# USB.net
KiCad netlist of a schematic drawn in Altium Designer
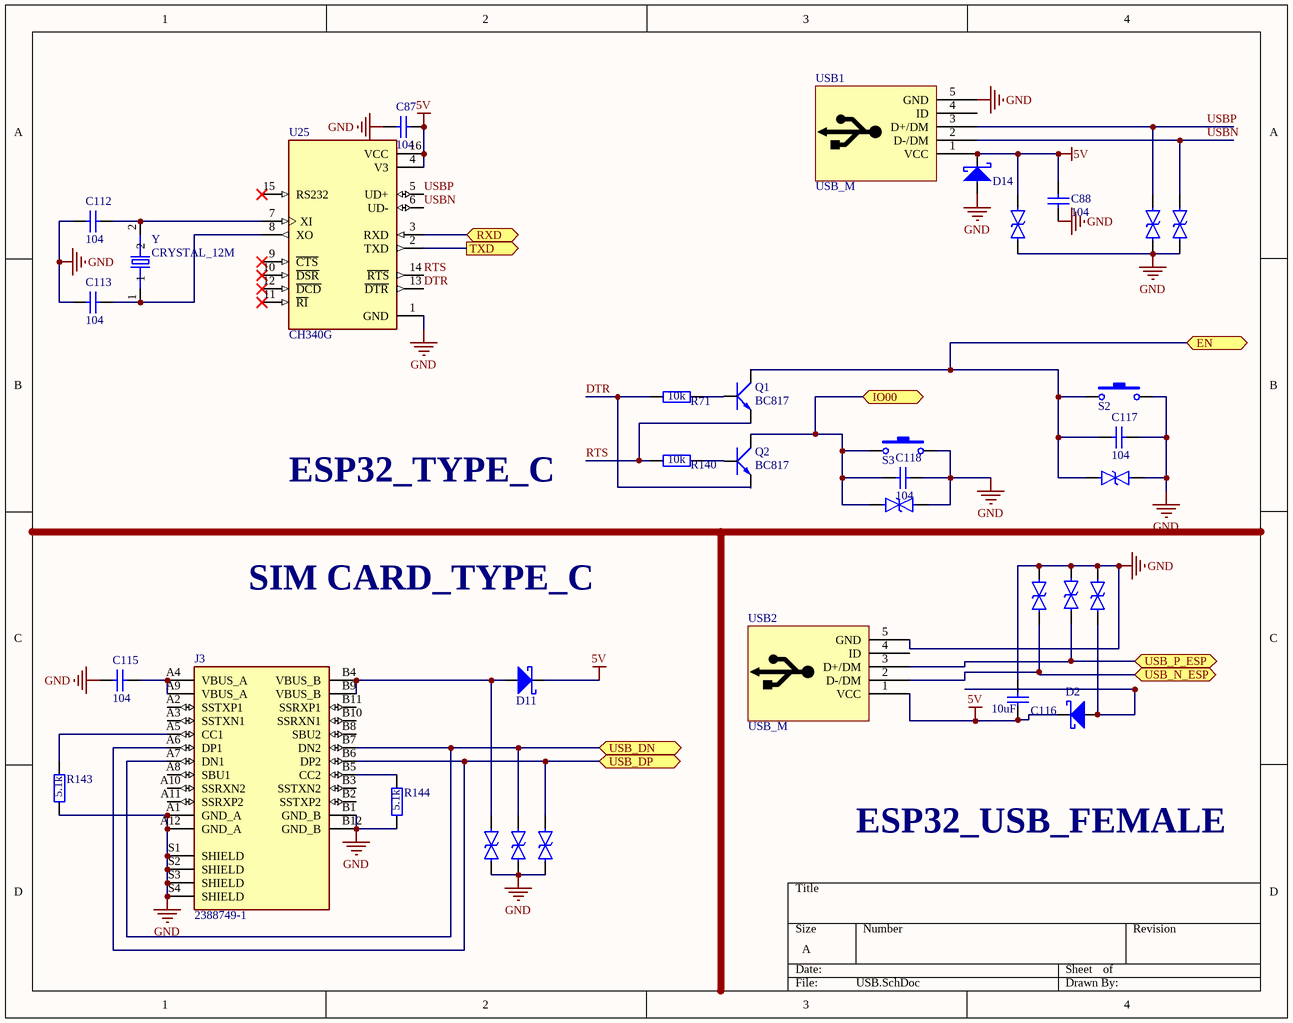
[diagram p0: USB.SchDoc]

(export (version "E")
  (design (tool "Eeschema 10.0.6"))
  (components
    (comp (ref "C87") (value "104") (footprint "0603_Cap") (libsource (lib "CMN") (part "Ceramic Capacitor")))
    (comp (ref "C88") (value "104") (footprint "0603_Cap") (libsource (lib "CMN") (part "Ceramic Capacitor")))
    (comp (ref "C112")
      (value "104")
      (footprint "0603_Cap")
      (libsource (lib "CMN") (part "Ceramic Capacitor"))
    )
    (comp (ref "C113")
      (value "104")
      (footprint "0603_Cap")
      (libsource (lib "CMN") (part "Ceramic Capacitor"))
    )
    (comp (ref "C115")
      (value "104")
      (footprint "0603_Cap")
      (libsource (lib "CMN") (part "Ceramic Capacitor"))
    )
    (comp (ref "C116")
      (value "10uF")
      (footprint "1206_CAP")
      (libsource (lib "CMN") (part "Ceramic Capacitor"))
    )
    (comp (ref "C117")
      (value "104")
      (footprint "0603_Cap")
      (libsource (lib "CMN") (part "Ceramic Capacitor"))
    )
    (comp (ref "C118")
      (value "104")
      (footprint "0603_Cap")
      (libsource (lib "CMN") (part "Ceramic Capacitor"))
    )
    (comp (ref "D2")
      (value "SS24")
      (footprint "DIO-SMD-106")
      (description "Diode Schottky")
      (fields (field (name "PART NUMBER") "LED 3 ly Single Colour"))
      (libsource (lib "KhanhBK_Library_4") (part "Diode Schottky"))
    )
    (comp (ref "D11")
      (value "SS24")
      (footprint "DIO-SMD-106")
      (description "Diode Schottky")
      (fields (field (name "PART NUMBER") "LED 3 ly Single Colour"))
      (libsource (lib "KhanhBK_Library_4") (part "Diode Schottky"))
    )
    (comp (ref "D14")
      (value "SS24")
      (footprint "DIO-SMD-106")
      (description "Diode Schottky")
      (fields (field (name "PART NUMBER") "LED 3 ly Single Colour"))
      (libsource (lib "KhanhBK_Library_4") (part "Diode Schottky"))
    )
    (comp (ref "J3")
      (value "2388749-1")
      (footprint "TE_2388749-1:USBC")
      (fields (field (name "MF") "TE Connectivity"))
      (libsource (lib "2388749-1") (part "2388749-1"))
    )
    (comp (ref "Q1")
      (value "BC817")
      (footprint "SOT-23")
      (description "SOT-23 - C8658")
      (libsource (lib "TranFet") (part "Trans BC817"))
    )
    (comp (ref "Q2")
      (value "BC817")
      (footprint "SOT-23")
      (description "SOT-23 - C8658")
      (libsource (lib "TranFet") (part "Trans BC817"))
    )
    (comp (ref "R71") (value "10k") (footprint "0603_Res") (libsource (lib "CMN") (part "Resistor")))
    (comp (ref "R140") (value "10k") (footprint "0603_Res") (libsource (lib "CMN") (part "Resistor")))
    (comp (ref "R143") (value "5.1k") (footprint "0603_Res") (libsource (lib "CMN") (part "Resistor")))
    (comp (ref "R144") (value "5.1k") (footprint "0603_Res") (libsource (lib "CMN") (part "Resistor")))
    (comp (ref "S2")
      (value "SW")
      (footprint "BUTTON-SMD 2PIN")
      (description "Switch-Button")
      (fields (field (name "PUBLISHER") "Altium Limited"))
      (libsource (lib "KhanhBK_Library_4") (part "SW-Button"))
    )
    (comp (ref "S3")
      (value "SW")
      (footprint "BUTTON-SMD 2PIN")
      (description "Switch-Button")
      (fields (field (name "PUBLISHER") "Altium Limited"))
      (libsource (lib "KhanhBK_Library_4") (part "SW-Button"))
    )
    (comp (ref "TVS5")
      (value "SMBJ12CA")
      (footprint "SMB - DO-214AA")
      (libsource (lib "CMN") (part "TVS Bi Diode"))
    )
    (comp (ref "TVS6")
      (value "SMBJ12CA")
      (footprint "SMB - DO-214AA")
      (libsource (lib "CMN") (part "TVS Bi Diode"))
    )
    (comp (ref "TVS9")
      (value "SMBJ12CA")
      (footprint "SMB - DO-214AA")
      (libsource (lib "CMN") (part "TVS Bi Diode"))
    )
    (comp (ref "TVS10")
      (value "SMBJ12CA")
      (footprint "SMB - DO-214AA")
      (libsource (lib "CMN") (part "TVS Bi Diode"))
    )
    (comp (ref "TVS11")
      (value "SMBJ12CA")
      (footprint "SMB - DO-214AA")
      (libsource (lib "CMN") (part "TVS Bi Diode"))
    )
    (comp (ref "TVS12")
      (value "SMBJ12CA")
      (footprint "SMB - DO-214AA")
      (libsource (lib "CMN") (part "TVS Bi Diode"))
    )
    (comp (ref "TVS18")
      (value "SMBJ12CA")
      (footprint "SMB - DO-214AA")
      (libsource (lib "CMN") (part "TVS Bi Diode"))
    )
    (comp (ref "TVS19")
      (value "SMBJ12CA")
      (footprint "SMB - DO-214AA")
      (libsource (lib "CMN") (part "TVS Bi Diode"))
    )
    (comp (ref "TVS20")
      (value "SMBJ12CA")
      (footprint "SMB - DO-214AA")
      (libsource (lib "CMN") (part "TVS Bi Diode"))
    )
    (comp (ref "TVS26")
      (value "SMBJ12CA")
      (footprint "SMB - DO-214AA")
      (libsource (lib "CMN") (part "TVS Bi Diode"))
    )
    (comp (ref "TVS27")
      (value "SMBJ12CA")
      (footprint "SMB - DO-214AA")
      (libsource (lib "CMN") (part "TVS Bi Diode"))
    )
    (comp (ref "U25")
      (value "CH340G")
      (footprint "SOIC127P600X180-16N")
      (description "USB Interface Integrated Circuit")
      (fields (field (name "MP") "Ch340G") (field (name "MF") "WCH"))
      (libsource (lib "CH340G") (part "CH340G"))
    )
    (comp (ref "USB1")
      (value "USB_M")
      (footprint "USB-M1")
      (libsource (lib "KhanhBK_Library_4") (part "USB_M"))
    )
    (comp (ref "USB2")
      (value "USB_M")
      (footprint "USB-M1")
      (libsource (lib "KhanhBK_Library_4") (part "USB_M"))
    )
    (comp (ref "Y")
      (value "CRYSTAL_12M")
      (footprint "CRYTAL_12M:XTAL1170X500X450")
      (description "HC49SDLF Series 12.288 MHz Â±30 ppm 20 pF -20 to +70 Â°C Resistance Weld Crystal")
      (fields (field (name "MF") "Fox Electronics") (field (name "MP") "FOXSDLF/128-20/TR"))
      (libsource (lib "Crystal_12M") (part "CRYSTAL_12M"))
    )
  )
  (nets
    (net (code "1") (name "/DTR") (class "Default")
      (node (ref "Q2") (pin "2") (pinfunction "E_2") (pintype "passive"))
      (node (ref "R71") (pin "1") (pinfunction "1_1") (pintype "passive"))
      (node (ref "U25") (pin "13") (pinfunction "~{DTR}_13") (pintype "output"))
    )
    (net (code "2") (name "/EN") (class "Default")
      (node (ref "C117") (pin "2") (pinfunction "2_2") (pintype "passive"))
      (node (ref "Q1") (pin "3") (pinfunction "C_3") (pintype "passive"))
      (node (ref "S2") (pin "1") (pinfunction "1_1") (pintype "passive"))
      (node (ref "TVS26") (pin "2") (pinfunction "2_2") (pintype "passive"))
    )
    (net (code "3") (name "/IO00") (class "Default")
      (node (ref "C118") (pin "2") (pinfunction "2_2") (pintype "passive"))
      (node (ref "Q2") (pin "3") (pinfunction "C_3") (pintype "passive"))
      (node (ref "S3") (pin "1") (pinfunction "1_1") (pintype "passive"))
      (node (ref "TVS27") (pin "2") (pinfunction "2_2") (pintype "passive"))
    )
    (net (code "4") (name "/RTS") (class "Default")
      (node (ref "Q1") (pin "2") (pinfunction "E_2") (pintype "passive"))
      (node (ref "R140") (pin "1") (pinfunction "1_1") (pintype "passive"))
      (node (ref "U25") (pin "14") (pinfunction "~{RTS}_14") (pintype "output"))
    )
    (net (code "5") (name "/RXD") (class "Default")
      (node (ref "U25") (pin "3") (pinfunction "RXD_3") (pintype "input"))
    )
    (net (code "6") (name "/TXD") (class "Default")
      (node (ref "U25") (pin "2") (pinfunction "TXD_2") (pintype "output"))
    )
    (net (code "7") (name "/USBN") (class "Default")
      (node (ref "TVS9") (pin "2") (pinfunction "2_2") (pintype "passive"))
      (node (ref "U25") (pin "6") (pinfunction "UD-_6") (pintype "bidirectional"))
      (node (ref "USB1") (pin "2") (pinfunction "D-/DM_2") (pintype "passive"))
    )
    (net (code "8") (name "/USBP") (class "Default")
      (node (ref "TVS6") (pin "2") (pinfunction "2_2") (pintype "passive"))
      (node (ref "U25") (pin "5") (pinfunction "UD+_5") (pintype "bidirectional"))
      (node (ref "USB1") (pin "3") (pinfunction "D+/DM_3") (pintype "passive"))
    )
    (net (code "9") (name "/USB_DN") (class "Default")
      (node (ref "J3") (pin "A7") (pinfunction "DN1_A7") (pintype "bidirectional"))
      (node (ref "J3") (pin "B7") (pinfunction "DN2_B7") (pintype "bidirectional"))
      (node (ref "TVS19") (pin "2") (pinfunction "2_2") (pintype "passive"))
    )
    (net (code "10") (name "/USB_DP") (class "Default")
      (node (ref "J3") (pin "A6") (pinfunction "DP1_A6") (pintype "bidirectional"))
      (node (ref "J3") (pin "B6") (pinfunction "DP2_B6") (pintype "bidirectional"))
      (node (ref "TVS20") (pin "2") (pinfunction "2_2") (pintype "passive"))
    )
    (net (code "11") (name "/USB_N_ESP") (class "Default")
      (node (ref "TVS10") (pin "2") (pinfunction "2_2") (pintype "passive"))
      (node (ref "USB2") (pin "2") (pinfunction "D-/DM_2") (pintype "passive"))
    )
    (net (code "12") (name "/USB_P_ESP") (class "Default")
      (node (ref "TVS11") (pin "2") (pinfunction "2_2") (pintype "passive"))
      (node (ref "USB2") (pin "3") (pinfunction "D+/DM_3") (pintype "passive"))
    )
    (net (code "13") (name "5V") (class "Default")
      (node (ref "C116") (pin "2") (pinfunction "2_2") (pintype "passive"))
      (node (ref "C87") (pin "2") (pinfunction "2_2") (pintype "passive"))
      (node (ref "C88") (pin "1") (pinfunction "1_1") (pintype "passive"))
      (node (ref "D11") (pin "2") (pinfunction "2_2") (pintype "passive"))
      (node (ref "D14") (pin "2") (pinfunction "2_2") (pintype "passive"))
      (node (ref "D2") (pin "2") (pinfunction "2_2") (pintype "passive"))
      (node (ref "TVS5") (pin "2") (pinfunction "2_2") (pintype "passive"))
      (node (ref "U25") (pin "16") (pinfunction "VCC_16") (pintype "power_in"))
      (node (ref "U25") (pin "4") (pinfunction "V3_4") (pintype "power_in"))
      (node (ref "USB1") (pin "1") (pinfunction "VCC_1") (pintype "passive"))
      (node (ref "USB2") (pin "1") (pinfunction "VCC_1") (pintype "passive"))
    )
    (net (code "14") (name "GND") (class "Default")
      (node (ref "C112") (pin "2") (pinfunction "2_2") (pintype "passive"))
      (node (ref "C113") (pin "2") (pinfunction "2_2") (pintype "passive"))
      (node (ref "C115") (pin "1") (pinfunction "1_1") (pintype "passive"))
      (node (ref "C116") (pin "1") (pinfunction "1_1") (pintype "passive"))
      (node (ref "C117") (pin "1") (pinfunction "1_1") (pintype "passive"))
      (node (ref "C118") (pin "1") (pinfunction "1_1") (pintype "passive"))
      (node (ref "C87") (pin "1") (pinfunction "1_1") (pintype "passive"))
      (node (ref "C88") (pin "2") (pinfunction "2_2") (pintype "passive"))
      (node (ref "D14") (pin "1") (pinfunction "1_1") (pintype "passive"))
      (node (ref "J3") (pin "A1") (pinfunction "GND_A_A1") (pintype "power_in"))
      (node (ref "J3") (pin "A12") (pinfunction "GND_A_A12") (pintype "power_in"))
      (node (ref "J3") (pin "B1") (pinfunction "GND_B_B1") (pintype "power_in"))
      (node (ref "J3") (pin "B12") (pinfunction "GND_B_B12") (pintype "power_in"))
      (node (ref "J3") (pin "S1") (pinfunction "SHIELD_S1") (pintype "passive"))
      (node (ref "J3") (pin "S2") (pinfunction "SHIELD_S2") (pintype "passive"))
      (node (ref "J3") (pin "S3") (pinfunction "SHIELD_S3") (pintype "passive"))
      (node (ref "J3") (pin "S4") (pinfunction "SHIELD_S4") (pintype "passive"))
      (node (ref "R143") (pin "1") (pinfunction "1_1") (pintype "passive"))
      (node (ref "R144") (pin "1") (pinfunction "1_1") (pintype "passive"))
      (node (ref "S2") (pin "2") (pinfunction "2_2") (pintype "passive"))
      (node (ref "S3") (pin "2") (pinfunction "2_2") (pintype "passive"))
      (node (ref "TVS10") (pin "1") (pinfunction "1_1") (pintype "passive"))
      (node (ref "TVS11") (pin "1") (pinfunction "1_1") (pintype "passive"))
      (node (ref "TVS12") (pin "1") (pinfunction "1_1") (pintype "passive"))
      (node (ref "TVS18") (pin "1") (pinfunction "1_1") (pintype "passive"))
      (node (ref "TVS19") (pin "1") (pinfunction "1_1") (pintype "passive"))
      (node (ref "TVS20") (pin "1") (pinfunction "1_1") (pintype "passive"))
      (node (ref "TVS26") (pin "1") (pinfunction "1_1") (pintype "passive"))
      (node (ref "TVS27") (pin "1") (pinfunction "1_1") (pintype "passive"))
      (node (ref "TVS5") (pin "1") (pinfunction "1_1") (pintype "passive"))
      (node (ref "TVS6") (pin "1") (pinfunction "1_1") (pintype "passive"))
      (node (ref "TVS9") (pin "1") (pinfunction "1_1") (pintype "passive"))
      (node (ref "U25") (pin "1") (pinfunction "GND_1") (pintype "power_in"))
      (node (ref "USB1") (pin "5") (pinfunction "GND_5") (pintype "passive"))
      (node (ref "USB2") (pin "5") (pinfunction "GND_5") (pintype "passive"))
    )
    (net (code "15") (name "Net-(C115-Pad2)") (class "Default")
      (node (ref "C115") (pin "2") (pinfunction "2_2") (pintype "passive"))
      (node (ref "J3") (pin "A4") (pinfunction "VBUS_A_A4") (pintype "power_in"))
      (node (ref "J3") (pin "A9") (pinfunction "VBUS_A_A9") (pintype "power_in"))
    )
    (net (code "16") (name "Net-(D2-Pad1)") (class "Default")
      (node (ref "D2") (pin "1") (pinfunction "1_1") (pintype "passive"))
      (node (ref "TVS12") (pin "2") (pinfunction "2_2") (pintype "passive"))
    )
    (net (code "17") (name "Net-(D11-Pad1)") (class "Default")
      (node (ref "D11") (pin "1") (pinfunction "1_1") (pintype "passive"))
      (node (ref "J3") (pin "B4") (pinfunction "VBUS_B_B4") (pintype "power_in"))
      (node (ref "J3") (pin "B9") (pinfunction "VBUS_B_B9") (pintype "power_in"))
      (node (ref "TVS18") (pin "2") (pinfunction "2_2") (pintype "passive"))
    )
    (net (code "18") (name "Net-(J3-CC1)") (class "Default")
      (node (ref "J3") (pin "A5") (pinfunction "CC1_A5") (pintype "bidirectional"))
      (node (ref "R143") (pin "2") (pinfunction "2_2") (pintype "passive"))
    )
    (net (code "19") (name "Net-(J3-CC2)") (class "Default")
      (node (ref "J3") (pin "B5") (pinfunction "CC2_B5") (pintype "bidirectional"))
      (node (ref "R144") (pin "2") (pinfunction "2_2") (pintype "passive"))
    )
    (net (code "20") (name "Net-(Q1-B)") (class "Default")
      (node (ref "Q1") (pin "1") (pinfunction "B_1") (pintype "passive"))
      (node (ref "R71") (pin "2") (pinfunction "2_2") (pintype "passive"))
    )
    (net (code "21") (name "Net-(Q2-B)") (class "Default")
      (node (ref "Q2") (pin "1") (pinfunction "B_1") (pintype "passive"))
      (node (ref "R140") (pin "2") (pinfunction "2_2") (pintype "passive"))
    )
    (net (code "22") (name "Net-(U25-XI)") (class "Default")
      (node (ref "C112") (pin "1") (pinfunction "1_1") (pintype "passive"))
      (node (ref "U25") (pin "7") (pinfunction "XI_7") (pintype "input"))
      (node (ref "Y") (pin "2") (pinfunction "2_2") (pintype "passive"))
    )
    (net (code "23") (name "Net-(U25-XO)") (class "Default")
      (node (ref "C113") (pin "1") (pinfunction "1_1") (pintype "passive"))
      (node (ref "U25") (pin "8") (pinfunction "XO_8") (pintype "output"))
      (node (ref "Y") (pin "1") (pinfunction "1_1") (pintype "passive"))
    )
    (net (code "24") (name "unconnected-(J3-SBU1-PadA8)") (class "Default")
      (node (ref "J3") (pin "A8") (pinfunction "SBU1_A8") (pintype "bidirectional"))
    )
    (net (code "25") (name "unconnected-(J3-SBU2-PadB8)") (class "Default")
      (node (ref "J3") (pin "B8") (pinfunction "SBU2_B8") (pintype "bidirectional"))
    )
    (net (code "26") (name "unconnected-(J3-SSRXN1-PadB10)") (class "Default")
      (node (ref "J3") (pin "B10") (pinfunction "SSRXN1_B10") (pintype "bidirectional"))
    )
    (net (code "27") (name "unconnected-(J3-SSRXN2-PadA10)") (class "Default")
      (node (ref "J3") (pin "A10") (pinfunction "SSRXN2_A10") (pintype "bidirectional"))
    )
    (net (code "28") (name "unconnected-(J3-SSRXP1-PadB11)") (class "Default")
      (node (ref "J3") (pin "B11") (pinfunction "SSRXP1_B11") (pintype "bidirectional"))
    )
    (net (code "29") (name "unconnected-(J3-SSRXP2-PadA11)") (class "Default")
      (node (ref "J3") (pin "A11") (pinfunction "SSRXP2_A11") (pintype "bidirectional"))
    )
    (net (code "30") (name "unconnected-(J3-SSTXN1-PadA3)") (class "Default")
      (node (ref "J3") (pin "A3") (pinfunction "SSTXN1_A3") (pintype "bidirectional"))
    )
    (net (code "31") (name "unconnected-(J3-SSTXN2-PadB3)") (class "Default")
      (node (ref "J3") (pin "B3") (pinfunction "SSTXN2_B3") (pintype "bidirectional"))
    )
    (net (code "32") (name "unconnected-(J3-SSTXP1-PadA2)") (class "Default")
      (node (ref "J3") (pin "A2") (pinfunction "SSTXP1_A2") (pintype "bidirectional"))
    )
    (net (code "33") (name "unconnected-(J3-SSTXP2-PadB2)") (class "Default")
      (node (ref "J3") (pin "B2") (pinfunction "SSTXP2_B2") (pintype "bidirectional"))
    )
    (net (code "34") (name "unconnected-(U25-RS232-Pad15)") (class "Default")
      (node (ref "U25") (pin "15") (pinfunction "RS232_15") (pintype "input+no_connect"))
    )
    (net (code "35") (name "unconnected-(U25-~{CTS}-Pad9)") (class "Default")
      (node (ref "U25") (pin "9") (pinfunction "~{CTS}_9") (pintype "input+no_connect"))
    )
    (net (code "36") (name "unconnected-(U25-~{DCD}-Pad12)") (class "Default")
      (node (ref "U25") (pin "12") (pinfunction "~{DCD}_12") (pintype "input+no_connect"))
    )
    (net (code "37") (name "unconnected-(U25-~{DSR}-Pad10)") (class "Default")
      (node (ref "U25") (pin "10") (pinfunction "~{DSR}_10") (pintype "input+no_connect"))
    )
    (net (code "38") (name "unconnected-(U25-~{RI}-Pad11)") (class "Default")
      (node (ref "U25") (pin "11") (pinfunction "~{RI}_11") (pintype "input+no_connect"))
    )
    (net (code "39") (name "unconnected-(USB1-ID-Pad4)") (class "Default")
      (node (ref "USB1") (pin "4") (pinfunction "ID_4") (pintype "passive"))
    )
    (net (code "40") (name "unconnected-(USB2-ID-Pad4)") (class "Default")
      (node (ref "USB2") (pin "4") (pinfunction "ID_4") (pintype "passive"))
    )
  )
)
